# simpleL6470_v2.net
KiCad netlist of a schematic drawn in EAGLE
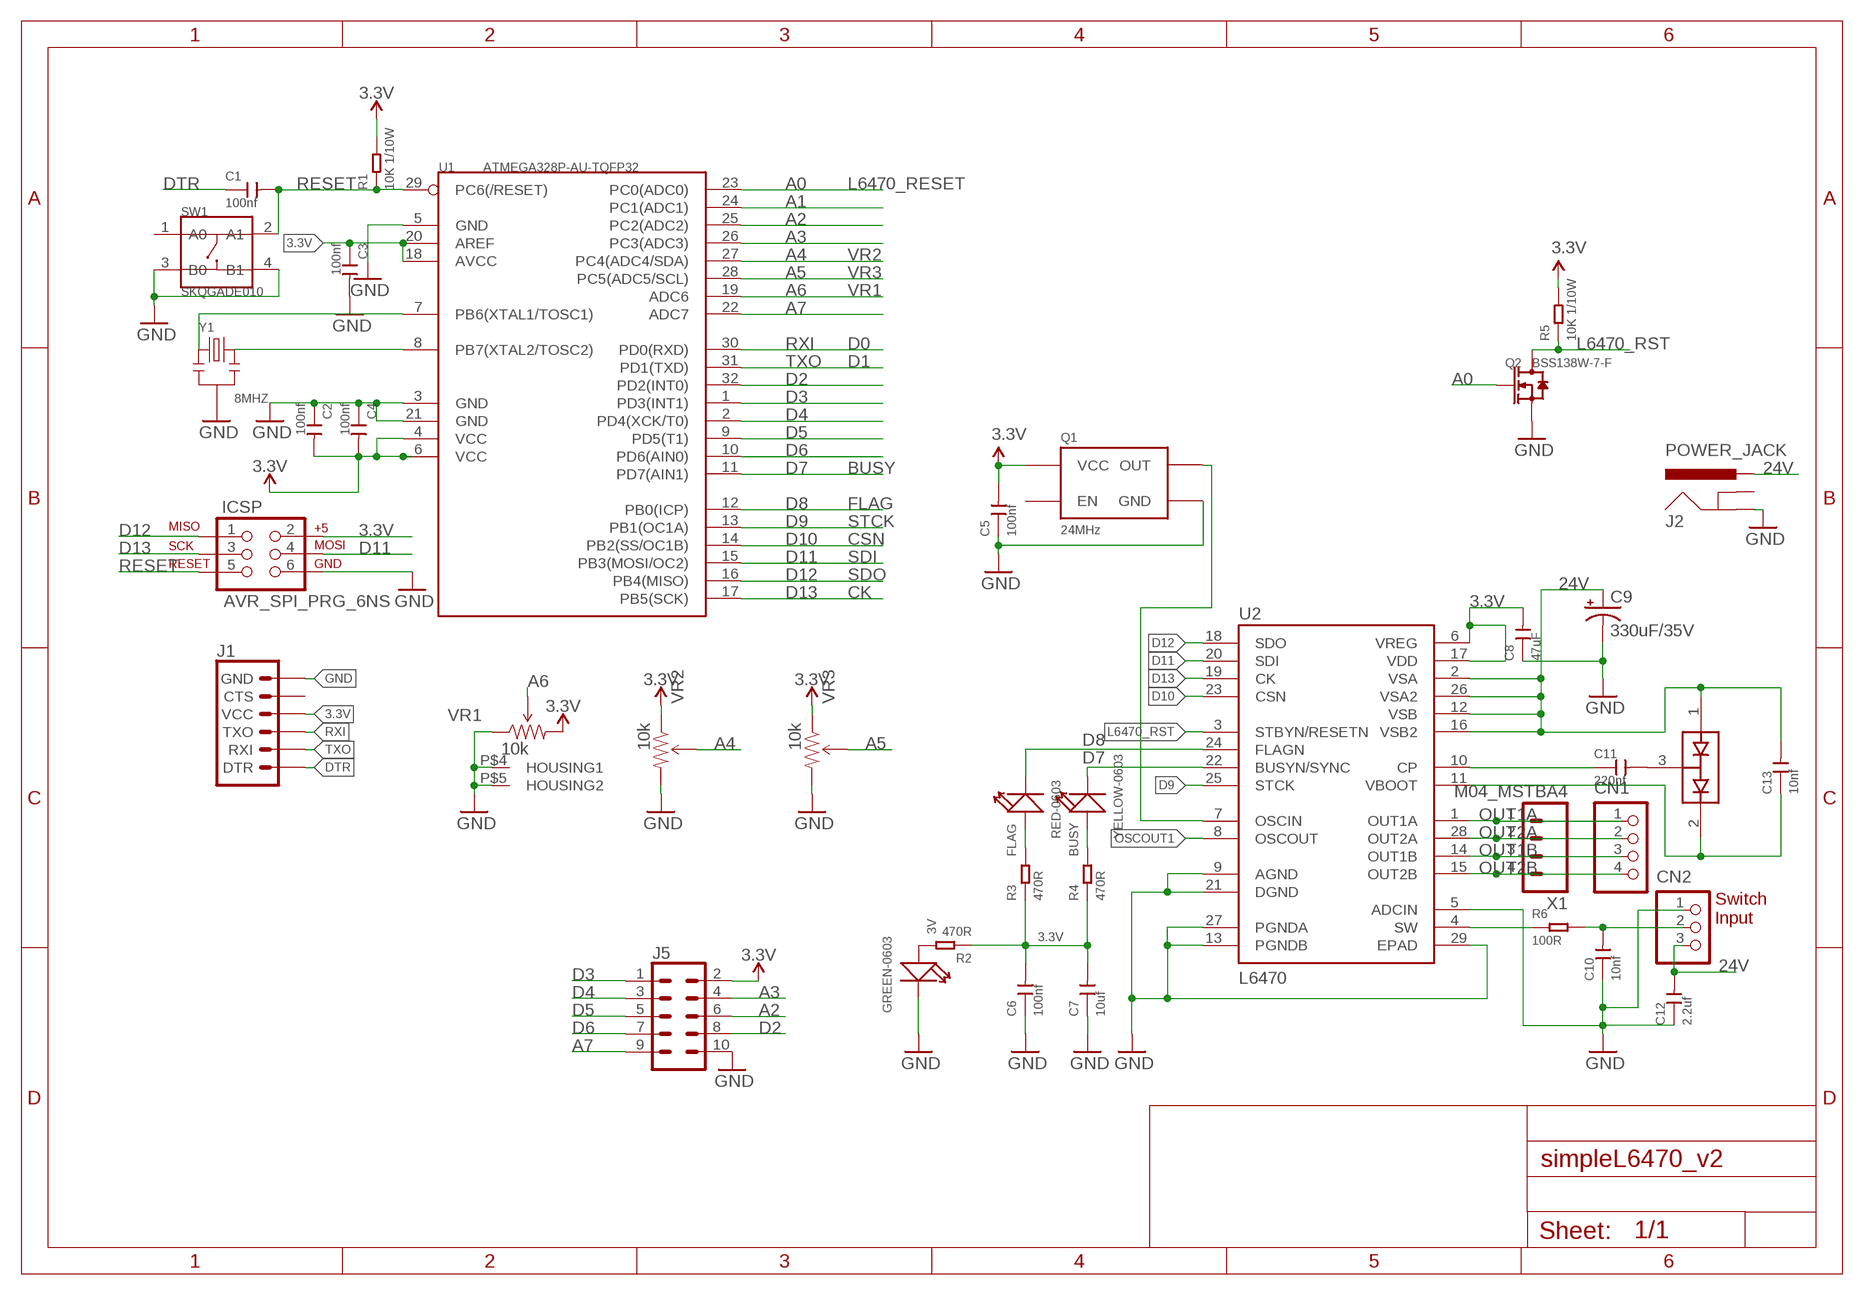
[diagram p0: schematic, sheet 1]

(export (version "E")
  (design (tool "Eeschema 10.0.6"))
  (components
    (comp (ref "3V")
      (value "GREEN-0603")
      (footprint "eagle-import:LED-0603")
      (fields (field (name "MPN") "19-217-G7C-AN1P2-3T"))
      (libsource (lib "eagle-import") (part "SMD-LED-CLEAR-GREEN(0603)"))
    )
    (comp (ref "BUSY")
      (value "YELLOW-0603")
      (footprint "eagle-import:LED-0603")
      (fields (field (name "MPN") "19-217-Y5C-AM1N1VY-3T"))
      (libsource (lib "eagle-import") (part "SMD-LED-CLEAR-YELLOW(0603)"))
    )
    (comp (ref "C1")
      (value "100nf")
      (footprint "eagle-import:C0603")
      (fields (field (name "MPN") "CC0603KRX7R9BB104"))
      (libsource (lib "eagle-import") (part "CERAMIC-100NF-50V-10%-X7R(0603)"))
    )
    (comp (ref "C2")
      (value "100nf")
      (footprint "eagle-import:C0603")
      (fields (field (name "MPN") "CC0603KRX7R9BB104"))
      (libsource (lib "eagle-import") (part "CERAMIC-100NF-50V-10%-X7R(0603)"))
    )
    (comp (ref "C3")
      (value "100nf")
      (footprint "eagle-import:C0603")
      (fields (field (name "MPN") "CC0603KRX7R9BB104"))
      (libsource (lib "eagle-import") (part "CERAMIC-100NF-50V-10%-X7R(0603)"))
    )
    (comp (ref "C4")
      (value "100nf")
      (footprint "eagle-import:C0603")
      (fields (field (name "MPN") "CC0603KRX7R9BB104"))
      (libsource (lib "eagle-import") (part "CERAMIC-100NF-50V-10%-X7R(0603)"))
    )
    (comp (ref "C5")
      (value "100nf")
      (footprint "eagle-import:C0603")
      (fields (field (name "MPN") "CC0603KRX7R9BB104"))
      (libsource (lib "eagle-import") (part "Seeed-Capacitor_464_CERAMIC-100NF-50V-10%-X7R(0603)"))
    )
    (comp (ref "C6")
      (value "100nf")
      (footprint "eagle-import:C0603")
      (fields (field (name "MPN") "CC0603KRX7R9BB104"))
      (libsource (lib "eagle-import") (part "Seeed-Capacitor_464_CERAMIC-100NF-50V-10%-X7R(0603)"))
    )
    (comp (ref "C7")
      (value "10uf")
      (footprint "eagle-import:C0805")
      (fields (field (name "MPN") "CC0805ZKY5V6BB106"))
      (libsource (lib "eagle-import") (part "CERAMIC-10UF-10V-(-20%～+80%)-Y5V(0805)"))
    )
    (comp (ref "C8")
      (value "47uF")
      (footprint "eagle-import:C1206")
      (fields (field (name "MPN") "GRM31CR60J107ME39L"))
      (libsource (lib "eagle-import") (part "CERAMIC-100UF-6.3V-20%-X5R(1206)"))
    )
    (comp (ref "C9")
      (value "330uF/35V")
      (footprint "eagle-import:NICHICON_D10")
      (libsource (lib "eagle-import") (part "C_POLD10"))
    )
    (comp (ref "C10")
      (value "10nf")
      (footprint "eagle-import:C0603")
      (fields (field (name "MPN") "CC0603KRX7R9BB103"))
      (libsource (lib "eagle-import") (part "CERAMIC-10NF-50V-10%-X7R(0603)"))
    )
    (comp (ref "C11")
      (value "220nf")
      (footprint "eagle-import:C0603")
      (fields (field (name "MPN") "CC0603KRX7R8BB224"))
      (libsource (lib "eagle-import") (part "CERAMIC-220NF-25V-10%-X7R(0603)"))
    )
    (comp (ref "C12")
      (value "2.2uf")
      (footprint "eagle-import:C0805")
      (fields (field (name "MPN") "CC0805KKX7R8BB225"))
      (libsource (lib "eagle-import") (part "CERAMIC-2.2UF-25V-10%-X7R(0805)"))
    )
    (comp (ref "C13")
      (value "10nf")
      (footprint "eagle-import:C0402")
      (fields (field (name "MPN") "CC0402KRX7R9BB103"))
      (libsource (lib "eagle-import") (part "CERAMIC-10NF-50V-10%-X7R(0402)"))
    )
    (comp (ref "CN1")
      (value "S4B-XASK-1")
      (footprint "eagle-import:S4B-XASK-1")
      (libsource (lib "eagle-import") (part "S4B-XASK-1"))
    )
    (comp (ref "CN2")
      (value "B3B-XASK-1")
      (footprint "eagle-import:B3B-XASK-1")
      (libsource (lib "eagle-import") (part "B3B-XASK-1"))
    )
    (comp (ref "D4")
      (value "BAV99")
      (footprint "eagle-import:SOT23")
      (libsource (lib "eagle-import") (part "BAV99"))
    )
    (comp (ref "FLAG")
      (value "RED-0603")
      (footprint "eagle-import:LED-0603")
      (fields (field (name "MPN") "19-217-R6C-AL1M2VY-3T"))
      (libsource (lib "eagle-import") (part "LED-SMD-RED-DIFFUSED(0603)"))
    )
    (comp (ref "ICSP")
      (value "AVR_SPI_PRG_6NS")
      (footprint "eagle-import:2X3-NS")
      (libsource (lib "eagle-import") (part "AVR_SPI_PRG_6NS"))
    )
    (comp (ref "J1")
      (value "6_PIN_SERIAL_TARGETLOCK")
      (footprint "eagle-import:1X06_LOCK")
      (libsource (lib "eagle-import") (part "6_PIN_SERIAL_TARGETLOCK"))
    )
    (comp (ref "J2")
      (value "POWER_JACK")
      (footprint "eagle-import:POWER_JACK_PTH")
      (libsource (lib "eagle-import") (part "POWER_JACK"))
    )
    (comp (ref "J5")
      (value "CONN_05X2NO_SILK")
      (footprint "eagle-import:2X5_NOSILK")
      (libsource (lib "eagle-import") (part "CONN_05X2NO_SILK"))
    )
    (comp (ref "Q1")
      (value "24MHz")
      (footprint "eagle-import:CRYSTAL-OSC-SMD-3.2X2.5")
      (libsource (lib "eagle-import") (part "CRYSTAL_OSC3.2X2.5"))
    )
    (comp (ref "Q2")
      (value "BSS138W-7-F")
      (footprint "eagle-import:SOT-23")
      (libsource (lib "eagle-import") (part "SMD-MOSFET-N-CH-50V-200MA-BSS138W-7-F(SOT-23)"))
    )
    (comp (ref "R1")
      (value "10K 1/10W")
      (footprint "eagle-import:R0603")
      (fields (field (name "MPN") "RC0603JR-0710KL"))
      (libsource (lib "eagle-import") (part "SMD-RES-10K-5%-1/10W(0603)"))
    )
    (comp (ref "R2")
      (value "470R")
      (footprint "eagle-import:R0603")
      (fields (field (name "MPN") "RC0603JR-07470RL"))
      (libsource (lib "eagle-import") (part "SMD-RES-470R-5%-1/10W(0603)"))
    )
    (comp (ref "R3")
      (value "470R")
      (footprint "eagle-import:R0603")
      (fields (field (name "MPN") "RC0603JR-07470RL"))
      (libsource (lib "eagle-import") (part "SMD-RES-470R-5%-1/10W(0603)"))
    )
    (comp (ref "R4")
      (value "470R")
      (footprint "eagle-import:R0603")
      (fields (field (name "MPN") "RC0603JR-07470RL"))
      (libsource (lib "eagle-import") (part "SMD-RES-470R-5%-1/10W(0603)"))
    )
    (comp (ref "R5")
      (value "10K 1/10W")
      (footprint "eagle-import:R0603")
      (fields (field (name "MPN") "RC0603JR-0710KL"))
      (libsource (lib "eagle-import") (part "Seeed-Resistor_474_SMD-RES-10K-5%-1/10W(0603)"))
    )
    (comp (ref "R6")
      (value "100R")
      (footprint "eagle-import:R0603")
      (fields (field (name "MPN") "RC0603JR-07100RL"))
      (libsource (lib "eagle-import") (part "SMD-RES-100R-5%-1/10W(0603)"))
    )
    (comp (ref "SW1")
      (value "SKQGADE010")
      (footprint "eagle-import:SW4-SMD-5.2X5.2X1.5MM")
      (libsource (lib "eagle-import") (part "SMD-BUTTON(4P-5.2X5.2X1.5MM-SKQGADE010)-SKQGADE010"))
    )
    (comp (ref "U1")
      (value "ATMEGA328P-AU-TQFP32")
      (footprint "eagle-import:TQFP32-0.8-7X7MM")
      (fields (field (name "MPN") "ATMEGA328P-AU"))
      (libsource (lib "eagle-import") (part "MCU-ATMEGA328P-AU(TQFP32)"))
    )
    (comp (ref "U2")
      (value "L6470")
      (footprint "eagle-import:HTSSOP28_NO_THERMAL")
      (libsource (lib "eagle-import") (part "L6470_NO_THERMAL"))
    )
    (comp (ref "VR1")
      (value "10k")
      (footprint "eagle-import:RK09")
      (libsource (lib "eagle-import") (part "TRIMVR_HOUSING_RK09"))
    )
    (comp (ref "VR2")
      (value "10k")
      (footprint "eagle-import:TRIMMER_T73XX")
      (libsource (lib "eagle-import") (part "TRIMVR_T73XX"))
    )
    (comp (ref "VR3")
      (value "10k")
      (footprint "eagle-import:TRIMMER_T73XX")
      (libsource (lib "eagle-import") (part "TRIMVR_T73XX"))
    )
    (comp (ref "X1")
      (value "M04_MSTBA4")
      (footprint "eagle-import:MSTBA4")
      (libsource (lib "eagle-import") (part "M04_MSTBA4"))
    )
    (comp (ref "Y1")
      (value "8MHZ")
      (footprint "eagle-import:X3-SMD-3.6X1.3X0.8MM")
      (libsource (lib "eagle-import") (part "SMD-CRYSTAL-8MHZ--0.3%-150R(3P-3.6X1.3MM)"))
    )
  )
  (nets
    (net (code "1") (name "/24V") (class "Default")
      (node (ref "C12") (pin "2") (pinfunction "2_2") (pintype "passive"))
      (node (ref "C13") (pin "2") (pinfunction "2_2") (pintype "passive"))
      (node (ref "C9") (pin "+") (pinfunction "+_+") (pintype "passive"))
      (node (ref "CN2") (pin "3") (pinfunction "3_3") (pintype "passive"))
      (node (ref "D4") (pin "1") (pinfunction "A1_1") (pintype "bidirectional"))
      (node (ref "J2") (pin "PWR") (pinfunction "PWR_PWR") (pintype "bidirectional"))
      (node (ref "U2") (pin "12") (pinfunction "VSB_12") (pintype "bidirectional"))
      (node (ref "U2") (pin "16") (pinfunction "VSB2_16") (pintype "bidirectional"))
      (node (ref "U2") (pin "2") (pinfunction "VSA_2") (pintype "bidirectional"))
      (node (ref "U2") (pin "26") (pinfunction "VSA2_26") (pintype "bidirectional"))
    )
    (net (code "2") (name "/A0") (class "Default")
      (node (ref "Q2") (pin "1") (pinfunction "G_1") (pintype "passive"))
      (node (ref "U1") (pin "23") (pinfunction "PC0(ADC0)_23") (pintype "bidirectional"))
    )
    (net (code "3") (name "/A1") (class "Default")
      (node (ref "U1") (pin "24") (pinfunction "PC1(ADC1)_24") (pintype "bidirectional"))
    )
    (net (code "4") (name "/A2") (class "Default")
      (node (ref "J5") (pin "6") (pinfunction "6_6") (pintype "passive"))
      (node (ref "U1") (pin "25") (pinfunction "PC2(ADC2)_25") (pintype "bidirectional"))
    )
    (net (code "5") (name "/A3") (class "Default")
      (node (ref "J5") (pin "4") (pinfunction "4_4") (pintype "passive"))
      (node (ref "U1") (pin "26") (pinfunction "PC3(ADC3)_26") (pintype "bidirectional"))
    )
    (net (code "6") (name "/A4") (class "Default")
      (node (ref "U1") (pin "27") (pinfunction "PC4(ADC4/SDA)_27") (pintype "bidirectional"))
      (node (ref "VR2") (pin "P$2") (pinfunction "WIPER_P$2") (pintype "passive"))
    )
    (net (code "7") (name "/A5") (class "Default")
      (node (ref "U1") (pin "28") (pinfunction "PC5(ADC5/SCL)_28") (pintype "bidirectional"))
      (node (ref "VR3") (pin "P$2") (pinfunction "WIPER_P$2") (pintype "passive"))
    )
    (net (code "8") (name "/A6") (class "Default")
      (node (ref "U1") (pin "19") (pinfunction "ADC6_19") (pintype "bidirectional"))
      (node (ref "VR1") (pin "2") (pinfunction "WIPER_2") (pintype "passive"))
    )
    (net (code "9") (name "/A7") (class "Default")
      (node (ref "J5") (pin "9") (pinfunction "9_9") (pintype "passive"))
      (node (ref "U1") (pin "22") (pinfunction "ADC7_22") (pintype "bidirectional"))
    )
    (net (code "10") (name "/D2") (class "Default")
      (node (ref "J5") (pin "8") (pinfunction "8_8") (pintype "passive"))
      (node (ref "U1") (pin "32") (pinfunction "PD2(INT0)_32") (pintype "bidirectional"))
    )
    (net (code "11") (name "/D3") (class "Default")
      (node (ref "J5") (pin "1") (pinfunction "1_1") (pintype "passive"))
      (node (ref "U1") (pin "1") (pinfunction "PD3(INT1)_1") (pintype "bidirectional"))
    )
    (net (code "12") (name "/D4") (class "Default")
      (node (ref "J5") (pin "3") (pinfunction "3_3") (pintype "passive"))
      (node (ref "U1") (pin "2") (pinfunction "PD4(XCK/T0)_2") (pintype "bidirectional"))
    )
    (net (code "13") (name "/D5") (class "Default")
      (node (ref "J5") (pin "5") (pinfunction "5_5") (pintype "passive"))
      (node (ref "U1") (pin "9") (pinfunction "PD5(T1)_9") (pintype "bidirectional"))
    )
    (net (code "14") (name "/D6") (class "Default")
      (node (ref "J5") (pin "7") (pinfunction "7_7") (pintype "passive"))
      (node (ref "U1") (pin "10") (pinfunction "PD6(AIN0)_10") (pintype "bidirectional"))
    )
    (net (code "15") (name "/D7") (class "Default")
      (node (ref "BUSY") (pin "-") (pinfunction "-_-") (pintype "passive"))
      (node (ref "U1") (pin "11") (pinfunction "PD7(AIN1)_11") (pintype "bidirectional"))
      (node (ref "U2") (pin "22") (pinfunction "BUSYN/SYNC_22") (pintype "bidirectional"))
    )
    (net (code "16") (name "/D8") (class "Default")
      (node (ref "FLAG") (pin "-") (pinfunction "-_-") (pintype "passive"))
      (node (ref "U1") (pin "12") (pinfunction "PB0(ICP)_12") (pintype "bidirectional"))
      (node (ref "U2") (pin "24") (pinfunction "FLAGN_24") (pintype "bidirectional"))
    )
    (net (code "17") (name "/OUT1A") (class "Default")
      (node (ref "CN1") (pin "1") (pinfunction "1_1") (pintype "passive"))
      (node (ref "U2") (pin "1") (pinfunction "OUT1A_1") (pintype "bidirectional"))
      (node (ref "X1") (pin "1") (pinfunction "1_1") (pintype "passive"))
    )
    (net (code "18") (name "/OUT1B") (class "Default")
      (node (ref "CN1") (pin "3") (pinfunction "3_3") (pintype "passive"))
      (node (ref "U2") (pin "14") (pinfunction "OUT1B_14") (pintype "bidirectional"))
      (node (ref "X1") (pin "3") (pinfunction "3_3") (pintype "passive"))
    )
    (net (code "19") (name "/OUT2A") (class "Default")
      (node (ref "CN1") (pin "2") (pinfunction "2_2") (pintype "passive"))
      (node (ref "U2") (pin "28") (pinfunction "OUT2A_28") (pintype "bidirectional"))
      (node (ref "X1") (pin "2") (pinfunction "2_2") (pintype "passive"))
    )
    (net (code "20") (name "/OUT2B") (class "Default")
      (node (ref "CN1") (pin "4") (pinfunction "4_4") (pintype "passive"))
      (node (ref "U2") (pin "15") (pinfunction "OUT2B_15") (pintype "bidirectional"))
      (node (ref "X1") (pin "4") (pinfunction "4_4") (pintype "passive"))
    )
    (net (code "21") (name "/RESET") (class "Default")
      (node (ref "C1") (pin "2") (pinfunction "2_2") (pintype "passive"))
      (node (ref "ICSP") (pin "5") (pinfunction "5_5") (pintype "passive"))
      (node (ref "R1") (pin "1") (pinfunction "1_1") (pintype "passive"))
      (node (ref "SW1") (pin "2") (pinfunction "A1_2") (pintype "bidirectional"))
      (node (ref "U1") (pin "29") (pinfunction "PC6(/RESET)_29") (pintype "bidirectional"))
    )
    (net (code "22") (name "3.3V") (class "Default")
      (node (ref "C2") (pin "2") (pinfunction "2_2") (pintype "passive"))
      (node (ref "C3") (pin "1") (pinfunction "1_1") (pintype "passive"))
      (node (ref "C4") (pin "2") (pinfunction "2_2") (pintype "passive"))
      (node (ref "C5") (pin "2") (pinfunction "2_2") (pintype "passive"))
      (node (ref "C6") (pin "2") (pinfunction "2_2") (pintype "passive"))
      (node (ref "C7") (pin "2") (pinfunction "2_2") (pintype "passive"))
      (node (ref "C8") (pin "2") (pinfunction "2_2") (pintype "passive"))
      (node (ref "ICSP") (pin "2") (pinfunction "2_2") (pintype "passive"))
      (node (ref "J1") (pin "4") (pinfunction "VCC_4") (pintype "passive"))
      (node (ref "J5") (pin "2") (pinfunction "2_2") (pintype "passive"))
      (node (ref "Q1") (pin "4") (pinfunction "VCC_4") (pintype "bidirectional"))
      (node (ref "R1") (pin "2") (pinfunction "2_2") (pintype "passive"))
      (node (ref "R2") (pin "1") (pinfunction "1_1") (pintype "passive"))
      (node (ref "R3") (pin "1") (pinfunction "1_1") (pintype "passive"))
      (node (ref "R4") (pin "1") (pinfunction "1_1") (pintype "passive"))
      (node (ref "R5") (pin "2") (pinfunction "2_2") (pintype "passive"))
      (node (ref "U1") (pin "18") (pinfunction "AVCC_18") (pintype "bidirectional"))
      (node (ref "U1") (pin "20") (pinfunction "AREF_20") (pintype "bidirectional"))
      (node (ref "U1") (pin "4") (pinfunction "VCC_4") (pintype "bidirectional"))
      (node (ref "U1") (pin "6") (pinfunction "VCC_6") (pintype "bidirectional"))
      (node (ref "U2") (pin "17") (pinfunction "VDD_17") (pintype "bidirectional"))
      (node (ref "U2") (pin "6") (pinfunction "VREG_6") (pintype "bidirectional"))
      (node (ref "VR1") (pin "3") (pinfunction "CW_3") (pintype "passive"))
      (node (ref "VR2") (pin "P$1") (pinfunction "CCW_P$1") (pintype "passive"))
      (node (ref "VR3") (pin "P$1") (pinfunction "CCW_P$1") (pintype "passive"))
    )
    (net (code "23") (name "D9") (class "Default")
      (node (ref "U1") (pin "13") (pinfunction "PB1(OC1A)_13") (pintype "bidirectional"))
      (node (ref "U2") (pin "25") (pinfunction "STCK_25") (pintype "bidirectional"))
    )
    (net (code "24") (name "D10") (class "Default")
      (node (ref "U1") (pin "14") (pinfunction "PB2(SS/OC1B)_14") (pintype "bidirectional"))
      (node (ref "U2") (pin "23") (pinfunction "CSN_23") (pintype "bidirectional"))
    )
    (net (code "25") (name "D11") (class "Default")
      (node (ref "ICSP") (pin "4") (pinfunction "4_4") (pintype "passive"))
      (node (ref "U1") (pin "15") (pinfunction "PB3(MOSI/OC2)_15") (pintype "bidirectional"))
      (node (ref "U2") (pin "20") (pinfunction "SDI_20") (pintype "bidirectional"))
    )
    (net (code "26") (name "D12") (class "Default")
      (node (ref "ICSP") (pin "1") (pinfunction "1_1") (pintype "passive"))
      (node (ref "U1") (pin "16") (pinfunction "PB4(MISO)_16") (pintype "bidirectional"))
      (node (ref "U2") (pin "18") (pinfunction "SDO_18") (pintype "bidirectional"))
    )
    (net (code "27") (name "D13") (class "Default")
      (node (ref "ICSP") (pin "3") (pinfunction "3_3") (pintype "passive"))
      (node (ref "U1") (pin "17") (pinfunction "PB5(SCK)_17") (pintype "bidirectional"))
      (node (ref "U2") (pin "19") (pinfunction "CK_19") (pintype "bidirectional"))
    )
    (net (code "28") (name "DTR") (class "Default")
      (node (ref "C1") (pin "1") (pinfunction "1_1") (pintype "passive"))
      (node (ref "J1") (pin "1") (pinfunction "DTR_1") (pintype "passive"))
    )
    (net (code "29") (name "GND") (class "Default")
      (node (ref "3V") (pin "-") (pinfunction "-_-") (pintype "passive"))
      (node (ref "C10") (pin "1") (pinfunction "1_1") (pintype "passive"))
      (node (ref "C12") (pin "1") (pinfunction "1_1") (pintype "passive"))
      (node (ref "C2") (pin "1") (pinfunction "1_1") (pintype "passive"))
      (node (ref "C3") (pin "2") (pinfunction "2_2") (pintype "passive"))
      (node (ref "C4") (pin "1") (pinfunction "1_1") (pintype "passive"))
      (node (ref "C5") (pin "1") (pinfunction "1_1") (pintype "passive"))
      (node (ref "C6") (pin "1") (pinfunction "1_1") (pintype "passive"))
      (node (ref "C7") (pin "1") (pinfunction "1_1") (pintype "passive"))
      (node (ref "C8") (pin "1") (pinfunction "1_1") (pintype "passive"))
      (node (ref "C9") (pin "-") (pinfunction "-_-") (pintype "passive"))
      (node (ref "CN2") (pin "1") (pinfunction "1_1") (pintype "passive"))
      (node (ref "ICSP") (pin "6") (pinfunction "6_6") (pintype "passive"))
      (node (ref "J1") (pin "6") (pinfunction "GND_6") (pintype "passive"))
      (node (ref "J2") (pin "GND") (pinfunction "GND_GND") (pintype "bidirectional"))
      (node (ref "J5") (pin "10") (pinfunction "10_10") (pintype "passive"))
      (node (ref "Q1") (pin "2") (pinfunction "GND_2") (pintype "bidirectional"))
      (node (ref "Q2") (pin "2") (pinfunction "S_2") (pintype "passive"))
      (node (ref "SW1") (pin "3") (pinfunction "B0_3") (pintype "bidirectional"))
      (node (ref "SW1") (pin "4") (pinfunction "B1_4") (pintype "bidirectional"))
      (node (ref "U1") (pin "21") (pinfunction "GND_21") (pintype "bidirectional"))
      (node (ref "U1") (pin "3") (pinfunction "GND_3") (pintype "bidirectional"))
      (node (ref "U1") (pin "5") (pinfunction "GND_5") (pintype "bidirectional"))
      (node (ref "U2") (pin "13") (pinfunction "PGNDB_13") (pintype "bidirectional"))
      (node (ref "U2") (pin "21") (pinfunction "DGND_21") (pintype "bidirectional"))
      (node (ref "U2") (pin "27") (pinfunction "PGNDA_27") (pintype "bidirectional"))
      (node (ref "U2") (pin "29") (pinfunction "EPAD_29") (pintype "bidirectional"))
      (node (ref "U2") (pin "5") (pinfunction "ADCIN_5") (pintype "bidirectional"))
      (node (ref "U2") (pin "9") (pinfunction "AGND_9") (pintype "bidirectional"))
      (node (ref "VR1") (pin "1") (pinfunction "CCW_1") (pintype "passive"))
      (node (ref "VR1") (pin "P$4") (pinfunction "HOUSING1_P$4") (pintype "passive"))
      (node (ref "VR1") (pin "P$5") (pinfunction "HOUSING2_P$5") (pintype "passive"))
      (node (ref "VR2") (pin "P$3") (pinfunction "CW_P$3") (pintype "passive"))
      (node (ref "VR3") (pin "P$3") (pinfunction "CW_P$3") (pintype "passive"))
      (node (ref "Y1") (pin "2") (pinfunction "2_2") (pintype "passive"))
    )
    (net (code "30") (name "L6470_RST") (class "Default")
      (node (ref "Q2") (pin "3") (pinfunction "D_3") (pintype "passive"))
      (node (ref "R5") (pin "1") (pinfunction "1_1") (pintype "passive"))
      (node (ref "U2") (pin "3") (pinfunction "STBYN/RESETN_3") (pintype "bidirectional"))
    )
    (net (code "31") (name "Net-(3V-Pad+)") (class "Default")
      (node (ref "3V") (pin "+") (pinfunction "+_+") (pintype "passive"))
      (node (ref "R2") (pin "2") (pinfunction "2_2") (pintype "passive"))
    )
    (net (code "32") (name "Net-(BUSY-Pad+)") (class "Default")
      (node (ref "BUSY") (pin "+") (pinfunction "+_+") (pintype "passive"))
      (node (ref "R4") (pin "2") (pinfunction "2_2") (pintype "passive"))
    )
    (net (code "33") (name "Net-(C10-Pad2)") (class "Default")
      (node (ref "C10") (pin "2") (pinfunction "2_2") (pintype "passive"))
      (node (ref "CN2") (pin "2") (pinfunction "2_2") (pintype "passive"))
      (node (ref "R6") (pin "2") (pinfunction "2_2") (pintype "passive"))
    )
    (net (code "34") (name "Net-(D4-C2)") (class "Default")
      (node (ref "C13") (pin "1") (pinfunction "1_1") (pintype "passive"))
      (node (ref "D4") (pin "2") (pinfunction "C2_2") (pintype "bidirectional"))
      (node (ref "U2") (pin "11") (pinfunction "VBOOT_11") (pintype "bidirectional"))
    )
    (net (code "35") (name "Net-(D4-COM)") (class "Default")
      (node (ref "C11") (pin "2") (pinfunction "2_2") (pintype "passive"))
      (node (ref "D4") (pin "3") (pinfunction "COM_3") (pintype "bidirectional"))
    )
    (net (code "36") (name "Net-(FLAG-Pad+)") (class "Default")
      (node (ref "FLAG") (pin "+") (pinfunction "+_+") (pintype "passive"))
      (node (ref "R3") (pin "2") (pinfunction "2_2") (pintype "passive"))
    )
    (net (code "37") (name "Net-(Q1-OUT)") (class "Default")
      (node (ref "Q1") (pin "3") (pinfunction "OUT_3") (pintype "bidirectional"))
      (node (ref "U2") (pin "7") (pinfunction "OSCIN_7") (pintype "bidirectional"))
    )
    (net (code "38") (name "Net-(U1-PB6(XTAL1{slash}TOSC1))") (class "Default")
      (node (ref "U1") (pin "7") (pinfunction "PB6(XTAL1/TOSC1)_7") (pintype "bidirectional"))
      (node (ref "Y1") (pin "1") (pinfunction "1_1") (pintype "passive"))
    )
    (net (code "39") (name "Net-(U1-PB7(XTAL2{slash}TOSC2))") (class "Default")
      (node (ref "U1") (pin "8") (pinfunction "PB7(XTAL2/TOSC2)_8") (pintype "bidirectional"))
      (node (ref "Y1") (pin "3") (pinfunction "3_3") (pintype "passive"))
    )
    (net (code "40") (name "Net-(U2-CP)") (class "Default")
      (node (ref "C11") (pin "1") (pinfunction "1_1") (pintype "passive"))
      (node (ref "U2") (pin "10") (pinfunction "CP_10") (pintype "bidirectional"))
    )
    (net (code "41") (name "Net-(U2-SW)") (class "Default")
      (node (ref "R6") (pin "1") (pinfunction "1_1") (pintype "passive"))
      (node (ref "U2") (pin "4") (pinfunction "SW_4") (pintype "bidirectional"))
    )
    (net (code "42") (name "OSCOUT1") (class "Default")
      (node (ref "U2") (pin "8") (pinfunction "OSCOUT_8") (pintype "bidirectional"))
    )
    (net (code "43") (name "RXI") (class "Default")
      (node (ref "J1") (pin "3") (pinfunction "TXO_3") (pintype "passive"))
      (node (ref "U1") (pin "30") (pinfunction "PD0(RXD)_30") (pintype "bidirectional"))
    )
    (net (code "44") (name "TXO") (class "Default")
      (node (ref "J1") (pin "2") (pinfunction "RXI_2") (pintype "passive"))
      (node (ref "U1") (pin "31") (pinfunction "PD1(TXD)_31") (pintype "bidirectional"))
    )
    (net (code "45") (name "unconnected-(J1-CTS-Pad5)") (class "Default")
      (node (ref "J1") (pin "5") (pinfunction "CTS_5") (pintype "passive"))
    )
    (net (code "46") (name "unconnected-(J2-PadGNDBREAK)") (class "Default")
      (node (ref "J2") (pin "GNDBREAK") (pinfunction "GNDBREAK_GNDBREAK") (pintype "bidirectional"))
    )
    (net (code "47") (name "unconnected-(Q1-EN-Pad1)") (class "Default")
      (node (ref "Q1") (pin "1") (pinfunction "EN_1") (pintype "bidirectional"))
    )
    (net (code "48") (name "unconnected-(SW1-A0-Pad1)") (class "Default")
      (node (ref "SW1") (pin "1") (pinfunction "A0_1") (pintype "bidirectional"))
    )
  )
)
